# Sheet1.net
KiCad netlist of a schematic drawn in Altium Designer
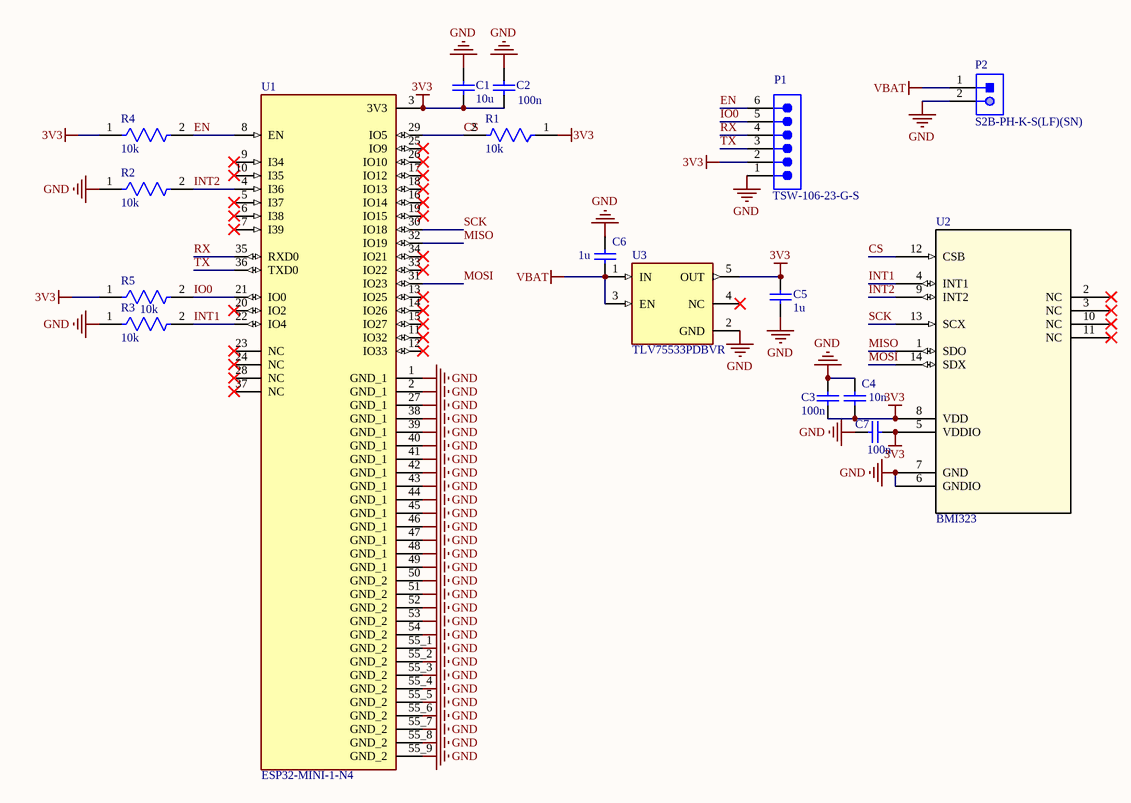
[diagram p0: Sheet1.SchDoc]

(export (version "E")
  (design (tool "Eeschema 10.0.6"))
  (components
    (comp (ref "C1")
      (value "10u")
      (footprint "CAPC2013X145X48NL20T23")
      (fields (field (name "MANUFACTURER") "Vitramon") (field (name "PART NUMBER") "VJ0805Y222JXAAC"))
      (libsource (lib "Altium Content Vault") (part "CAP"))
    )
    (comp (ref "C2")
      (value "100n")
      (footprint "CAPC2013X145X48NL20T23")
      (fields (field (name "MANUFACTURER") "Vitramon") (field (name "PART NUMBER") "VJ0805Y222JXAAC"))
      (libsource (lib "Altium Content Vault") (part "CAP"))
    )
    (comp (ref "C3")
      (value "100n")
      (footprint "CAPC2013X145X48NL20T23")
      (fields (field (name "MANUFACTURER") "Vitramon") (field (name "PART NUMBER") "VJ0805Y222JXAAC"))
      (libsource (lib "Altium Content Vault") (part "CAP"))
    )
    (comp (ref "C4")
      (value "10n")
      (footprint "CAPC2013X145X48NL20T23")
      (fields (field (name "MANUFACTURER") "Vitramon") (field (name "PART NUMBER") "VJ0805Y222JXAAC"))
      (libsource (lib "Altium Content Vault") (part "CAP"))
    )
    (comp (ref "C5")
      (value "1u")
      (footprint "CAPC2013X145X48NL20T23")
      (fields (field (name "MANUFACTURER") "Vitramon") (field (name "PART NUMBER") "VJ0805Y222JXAAC"))
      (libsource (lib "Altium Content Vault") (part "CAP"))
    )
    (comp (ref "C6")
      (value "1u")
      (footprint "CAPC2013X145X48NL20T23")
      (fields (field (name "MANUFACTURER") "Vitramon") (field (name "PART NUMBER") "VJ0805Y222JXAAC"))
      (libsource (lib "Altium Content Vault") (part "CAP"))
    )
    (comp (ref "C7")
      (value "100n")
      (footprint "CAPC2013X145X48NL20T23")
      (fields (field (name "MANUFACTURER") "Vitramon") (field (name "PART NUMBER") "VJ0805Y222JXAAC"))
      (libsource (lib "Altium Content Vault") (part "CAP"))
    )
    (comp (ref "P1")
      (value "TSW-106-23-G-S")
      (footprint "SMTC-TSW-106-23-X-S")
      (description "0.025\" SQ Post Header, Through-hole, Vertical, -55 to 125 degC, 2.54 mm Pitch, 6-Pin, Male, RoHS")
      (fields (field (name "MANUFACTURER") "Samtec"))
      (libsource (lib "Altium Content Vault") (part "SMTC-TSW-106-X-X-S-X"))
    )
    (comp (ref "P2")
      (value "S2B-PH-K-S(LF)(SN)")
      (footprint "JST-S2B-PH-K-S_V")
      (fields (field (name "TOLERANCE") "20%"))
      (libsource (lib "Altium Content Vault") (part "CN-1P-M-R2"))
    )
    (comp (ref "R1")
      (value "10k")
      (footprint "FP-MCU0805-IPC_B")
      (fields (field (name "TOLERANCE") "0.1%"))
      (libsource (lib "Altium Content Vault") (part "1029c3af85768c4190bb7ad29bc67b5"))
    )
    (comp (ref "R2")
      (value "10k")
      (footprint "FP-MCU0805-IPC_B")
      (description "RES 1.05K OHM 0.5% 1/5W 0805")
      (fields (field (name "TOLERANCE") "0.1%"))
      (libsource (lib "Altium Content Vault") (part "1029c3af85768c4190bb7ad29bc67b5"))
    )
    (comp (ref "R3")
      (value "10k")
      (footprint "FP-MCU0805-IPC_B")
      (description "RES 1.05K OHM 0.5% 1/5W 0805")
      (fields (field (name "TOLERANCE") "0.1%"))
      (libsource (lib "Altium Content Vault") (part "1029c3af85768c4190bb7ad29bc67b5"))
    )
    (comp (ref "R4")
      (value "10k")
      (footprint "FP-MCU0805-IPC_B")
      (description "RES 1.05K OHM 0.5% 1/5W 0805")
      (fields (field (name "TOLERANCE") "0.1%"))
      (libsource (lib "Altium Content Vault") (part "1029c3af85768c4190bb7ad29bc67b5"))
    )
    (comp (ref "R5")
      (value "10k")
      (footprint "FP-MCU0805-IPC_B")
      (description "RES 1.05K OHM 0.5% 1/5W 0805")
      (fields (field (name "TOLERANCE") "0.1%"))
      (libsource (lib "Altium Content Vault") (part "1029c3af85768c4190bb7ad29bc67b5"))
    )
    (comp (ref "U1")
      (value "ESP32-MINI-1-N4")
      (footprint "XCVR_ESP32-MINI-1-N4")
      (fields (field (name "MF") "Espressif Systems"))
      (libsource (lib "ESP32-MINI-1-N4") (part "ESP32-MINI-1-N4"))
    )
    (comp (ref "U2")
      (value "BMI323")
      (footprint "BMI323_BOS")
      (description "Description")
      (fields (field (name "COPYRIGHT") "Copyright (C) 2026 Ultra Librarian. All rights reserved."))
      (libsource (lib "BMI323") (part "BMI323"))
    )
    (comp (ref "U3")
      (value "TLV75533PDBVR")
      (footprint "FP-DBV0005A-MFG")
      (description "IC REG LINEAR 3.3V 500MA SOT23-5")
      (fields
        (field (name "MANUFACTURER") "Texas Instruments")
        (field (name "OCTOPART") "https://octopart.com/tlv75533pdbvr-texas+instruments-91272349")
      )
      (libsource (lib "Altium Content Vault") (part "bc27d4aa6bca38f00d7b0ca125c90e0"))
    )
  )
  (nets
    (net (code "1") (name "/CS") (class "Default")
      (node (ref "R1") (pin "2") (pinfunction "2_2") (pintype "passive"))
      (node (ref "U1") (pin "29") (pinfunction "IO5_29") (pintype "bidirectional"))
      (node (ref "U2") (pin "12") (pinfunction "CSB_12") (pintype "input"))
    )
    (net (code "2") (name "/EN") (class "Default")
      (node (ref "P1") (pin "6") (pinfunction "6_6") (pintype "passive"))
      (node (ref "R4") (pin "2") (pinfunction "2_2") (pintype "passive"))
      (node (ref "U1") (pin "8") (pinfunction "EN_8") (pintype "input"))
    )
    (net (code "3") (name "/INT1") (class "Default")
      (node (ref "R3") (pin "2") (pinfunction "2_2") (pintype "passive"))
      (node (ref "U1") (pin "22") (pinfunction "IO4_22") (pintype "bidirectional"))
      (node (ref "U2") (pin "4") (pinfunction "INT1_4") (pintype "bidirectional"))
    )
    (net (code "4") (name "/INT2") (class "Default")
      (node (ref "R2") (pin "2") (pinfunction "2_2") (pintype "passive"))
      (node (ref "U1") (pin "4") (pinfunction "I36_4") (pintype "input"))
      (node (ref "U2") (pin "9") (pinfunction "INT2_9") (pintype "bidirectional"))
    )
    (net (code "5") (name "/IO0") (class "Default")
      (node (ref "P1") (pin "5") (pinfunction "5_5") (pintype "passive"))
      (node (ref "R5") (pin "2") (pinfunction "2_2") (pintype "passive"))
      (node (ref "U1") (pin "21") (pinfunction "IO0_21") (pintype "bidirectional"))
    )
    (net (code "6") (name "/MISO") (class "Default")
      (node (ref "U1") (pin "32") (pinfunction "IO19_32") (pintype "bidirectional"))
      (node (ref "U2") (pin "1") (pinfunction "SDO_1") (pintype "bidirectional"))
    )
    (net (code "7") (name "/MOSI") (class "Default")
      (node (ref "U1") (pin "31") (pinfunction "IO23_31") (pintype "bidirectional"))
      (node (ref "U2") (pin "14") (pinfunction "SDX_14") (pintype "bidirectional"))
    )
    (net (code "8") (name "/RX") (class "Default")
      (node (ref "P1") (pin "4") (pinfunction "4_4") (pintype "passive"))
      (node (ref "U1") (pin "35") (pinfunction "RXD0_35") (pintype "bidirectional"))
    )
    (net (code "9") (name "/SCK") (class "Default")
      (node (ref "U1") (pin "30") (pinfunction "IO18_30") (pintype "bidirectional"))
      (node (ref "U2") (pin "13") (pinfunction "SCX_13") (pintype "input"))
    )
    (net (code "10") (name "/TX") (class "Default")
      (node (ref "P1") (pin "3") (pinfunction "3_3") (pintype "passive"))
      (node (ref "U1") (pin "36") (pinfunction "TXD0_36") (pintype "bidirectional"))
    )
    (net (code "11") (name "3V3") (class "Default")
      (node (ref "C1") (pin "1") (pinfunction "1_1") (pintype "passive"))
      (node (ref "C2") (pin "1") (pinfunction "1_1") (pintype "passive"))
      (node (ref "C3") (pin "1") (pinfunction "1_1") (pintype "passive"))
      (node (ref "C4") (pin "1") (pinfunction "1_1") (pintype "passive"))
      (node (ref "C5") (pin "1") (pinfunction "1_1") (pintype "passive"))
      (node (ref "C7") (pin "1") (pinfunction "1_1") (pintype "passive"))
      (node (ref "P1") (pin "2") (pinfunction "2_2") (pintype "passive"))
      (node (ref "R1") (pin "1") (pinfunction "1_1") (pintype "passive"))
      (node (ref "R4") (pin "1") (pinfunction "1_1") (pintype "passive"))
      (node (ref "R5") (pin "1") (pinfunction "1_1") (pintype "passive"))
      (node (ref "U1") (pin "3") (pinfunction "3V3_3") (pintype "power_in"))
      (node (ref "U2") (pin "5") (pinfunction "VDDIO_5") (pintype "power_in"))
      (node (ref "U2") (pin "8") (pinfunction "VDD_8") (pintype "power_in"))
      (node (ref "U3") (pin "5") (pinfunction "OUT_5") (pintype "output"))
    )
    (net (code "12") (name "GND") (class "Default")
      (node (ref "C1") (pin "2") (pinfunction "2_2") (pintype "passive"))
      (node (ref "C2") (pin "2") (pinfunction "2_2") (pintype "passive"))
      (node (ref "C3") (pin "2") (pinfunction "2_2") (pintype "passive"))
      (node (ref "C4") (pin "2") (pinfunction "2_2") (pintype "passive"))
      (node (ref "C5") (pin "2") (pinfunction "2_2") (pintype "passive"))
      (node (ref "C6") (pin "2") (pinfunction "2_2") (pintype "passive"))
      (node (ref "C7") (pin "2") (pinfunction "2_2") (pintype "passive"))
      (node (ref "P1") (pin "1") (pinfunction "1_1") (pintype "passive"))
      (node (ref "P2") (pin "2") (pinfunction "2_2") (pintype "passive"))
      (node (ref "R2") (pin "1") (pinfunction "1_1") (pintype "passive"))
      (node (ref "R3") (pin "1") (pinfunction "1_1") (pintype "passive"))
      (node (ref "U1") (pin "1") (pinfunction "GND_1_1") (pintype "power_in"))
      (node (ref "U1") (pin "2") (pinfunction "GND_1_2") (pintype "power_in"))
      (node (ref "U1") (pin "27") (pinfunction "GND_1_27") (pintype "power_in"))
      (node (ref "U1") (pin "38") (pinfunction "GND_1_38") (pintype "power_in"))
      (node (ref "U1") (pin "39") (pinfunction "GND_1_39") (pintype "power_in"))
      (node (ref "U1") (pin "40") (pinfunction "GND_1_40") (pintype "power_in"))
      (node (ref "U1") (pin "41") (pinfunction "GND_1_41") (pintype "power_in"))
      (node (ref "U1") (pin "42") (pinfunction "GND_1_42") (pintype "power_in"))
      (node (ref "U1") (pin "43") (pinfunction "GND_1_43") (pintype "power_in"))
      (node (ref "U1") (pin "44") (pinfunction "GND_1_44") (pintype "power_in"))
      (node (ref "U1") (pin "45") (pinfunction "GND_1_45") (pintype "power_in"))
      (node (ref "U1") (pin "46") (pinfunction "GND_1_46") (pintype "power_in"))
      (node (ref "U1") (pin "47") (pinfunction "GND_1_47") (pintype "power_in"))
      (node (ref "U1") (pin "48") (pinfunction "GND_1_48") (pintype "power_in"))
      (node (ref "U1") (pin "49") (pinfunction "GND_1_49") (pintype "power_in"))
      (node (ref "U1") (pin "50") (pinfunction "GND_2_50") (pintype "power_in"))
      (node (ref "U1") (pin "51") (pinfunction "GND_2_51") (pintype "power_in"))
      (node (ref "U1") (pin "52") (pinfunction "GND_2_52") (pintype "power_in"))
      (node (ref "U1") (pin "53") (pinfunction "GND_2_53") (pintype "power_in"))
      (node (ref "U1") (pin "54") (pinfunction "GND_2_54") (pintype "power_in"))
      (node (ref "U1") (pin "55_1") (pinfunction "GND_2_55_1") (pintype "power_in"))
      (node (ref "U1") (pin "55_2") (pinfunction "GND_2_55_2") (pintype "power_in"))
      (node (ref "U1") (pin "55_3") (pinfunction "GND_2_55_3") (pintype "power_in"))
      (node (ref "U1") (pin "55_4") (pinfunction "GND_2_55_4") (pintype "power_in"))
      (node (ref "U1") (pin "55_5") (pinfunction "GND_2_55_5") (pintype "power_in"))
      (node (ref "U1") (pin "55_6") (pinfunction "GND_2_55_6") (pintype "power_in"))
      (node (ref "U1") (pin "55_7") (pinfunction "GND_2_55_7") (pintype "power_in"))
      (node (ref "U1") (pin "55_8") (pinfunction "GND_2_55_8") (pintype "power_in"))
      (node (ref "U1") (pin "55_9") (pinfunction "GND_2_55_9") (pintype "power_in"))
      (node (ref "U2") (pin "6") (pinfunction "GNDIO_6") (pintype "power_in"))
      (node (ref "U2") (pin "7") (pinfunction "GND_7") (pintype "power_in"))
      (node (ref "U3") (pin "2") (pinfunction "GND_2") (pintype "power_in"))
    )
    (net (code "13") (name "VBAT") (class "Default")
      (node (ref "C6") (pin "1") (pinfunction "1_1") (pintype "passive"))
      (node (ref "P2") (pin "1") (pinfunction "1_1") (pintype "passive"))
      (node (ref "U3") (pin "1") (pinfunction "IN_1") (pintype "input"))
      (node (ref "U3") (pin "3") (pinfunction "EN_3") (pintype "input"))
    )
    (net (code "14") (name "unconnected-(U1-I34-Pad9)") (class "Default")
      (node (ref "U1") (pin "9") (pinfunction "I34_9") (pintype "input+no_connect"))
    )
    (net (code "15") (name "unconnected-(U1-I35-Pad10)") (class "Default")
      (node (ref "U1") (pin "10") (pinfunction "I35_10") (pintype "input+no_connect"))
    )
    (net (code "16") (name "unconnected-(U1-I37-Pad5)") (class "Default")
      (node (ref "U1") (pin "5") (pinfunction "I37_5") (pintype "input+no_connect"))
    )
    (net (code "17") (name "unconnected-(U1-I38-Pad6)") (class "Default")
      (node (ref "U1") (pin "6") (pinfunction "I38_6") (pintype "input+no_connect"))
    )
    (net (code "18") (name "unconnected-(U1-I39-Pad7)") (class "Default")
      (node (ref "U1") (pin "7") (pinfunction "I39_7") (pintype "input+no_connect"))
    )
    (net (code "19") (name "unconnected-(U1-IO2-Pad20)") (class "Default")
      (node (ref "U1") (pin "20") (pinfunction "IO2_20") (pintype "bidirectional+no_connect"))
    )
    (net (code "20") (name "unconnected-(U1-IO9-Pad25)") (class "Default")
      (node (ref "U1") (pin "25") (pinfunction "IO9_25") (pintype "bidirectional+no_connect"))
    )
    (net (code "21") (name "unconnected-(U1-IO10-Pad26)") (class "Default")
      (node (ref "U1") (pin "26") (pinfunction "IO10_26") (pintype "bidirectional+no_connect"))
    )
    (net (code "22") (name "unconnected-(U1-IO12-Pad17)") (class "Default")
      (node (ref "U1") (pin "17") (pinfunction "IO12_17") (pintype "bidirectional+no_connect"))
    )
    (net (code "23") (name "unconnected-(U1-IO13-Pad18)") (class "Default")
      (node (ref "U1") (pin "18") (pinfunction "IO13_18") (pintype "bidirectional+no_connect"))
    )
    (net (code "24") (name "unconnected-(U1-IO14-Pad16)") (class "Default")
      (node (ref "U1") (pin "16") (pinfunction "IO14_16") (pintype "bidirectional+no_connect"))
    )
    (net (code "25") (name "unconnected-(U1-IO15-Pad19)") (class "Default")
      (node (ref "U1") (pin "19") (pinfunction "IO15_19") (pintype "bidirectional+no_connect"))
    )
    (net (code "26") (name "unconnected-(U1-IO21-Pad34)") (class "Default")
      (node (ref "U1") (pin "34") (pinfunction "IO21_34") (pintype "bidirectional+no_connect"))
    )
    (net (code "27") (name "unconnected-(U1-IO22-Pad33)") (class "Default")
      (node (ref "U1") (pin "33") (pinfunction "IO22_33") (pintype "bidirectional+no_connect"))
    )
    (net (code "28") (name "unconnected-(U1-IO25-Pad13)") (class "Default")
      (node (ref "U1") (pin "13") (pinfunction "IO25_13") (pintype "bidirectional+no_connect"))
    )
    (net (code "29") (name "unconnected-(U1-IO26-Pad14)") (class "Default")
      (node (ref "U1") (pin "14") (pinfunction "IO26_14") (pintype "bidirectional+no_connect"))
    )
    (net (code "30") (name "unconnected-(U1-IO27-Pad15)") (class "Default")
      (node (ref "U1") (pin "15") (pinfunction "IO27_15") (pintype "bidirectional+no_connect"))
    )
    (net (code "31") (name "unconnected-(U1-IO32-Pad11)") (class "Default")
      (node (ref "U1") (pin "11") (pinfunction "IO32_11") (pintype "bidirectional+no_connect"))
    )
    (net (code "32") (name "unconnected-(U1-IO33-Pad12)") (class "Default")
      (node (ref "U1") (pin "12") (pinfunction "IO33_12") (pintype "bidirectional+no_connect"))
    )
    (net (code "33") (name "unconnected-(U1-NC-Pad23)") (class "Default")
      (node (ref "U1") (pin "23") (pinfunction "NC_23") (pintype "passive+no_connect"))
    )
    (net (code "34") (name "unconnected-(U1-NC-Pad24)") (class "Default")
      (node (ref "U1") (pin "24") (pinfunction "NC_24") (pintype "passive+no_connect"))
    )
    (net (code "35") (name "unconnected-(U1-NC-Pad28)") (class "Default")
      (node (ref "U1") (pin "28") (pinfunction "NC_28") (pintype "passive+no_connect"))
    )
    (net (code "36") (name "unconnected-(U1-NC-Pad37)") (class "Default")
      (node (ref "U1") (pin "37") (pinfunction "NC_37") (pintype "passive+no_connect"))
    )
    (net (code "37") (name "unconnected-(U2-NC-Pad2)") (class "Default")
      (node (ref "U2") (pin "2") (pinfunction "NC_2") (pintype "passive+no_connect"))
    )
    (net (code "38") (name "unconnected-(U2-NC-Pad3)") (class "Default")
      (node (ref "U2") (pin "3") (pinfunction "NC_3") (pintype "passive+no_connect"))
    )
    (net (code "39") (name "unconnected-(U2-NC-Pad10)") (class "Default")
      (node (ref "U2") (pin "10") (pinfunction "NC_10") (pintype "passive+no_connect"))
    )
    (net (code "40") (name "unconnected-(U2-NC-Pad11)") (class "Default")
      (node (ref "U2") (pin "11") (pinfunction "NC_11") (pintype "passive+no_connect"))
    )
    (net (code "41") (name "unconnected-(U3-NC-Pad4)") (class "Default")
      (node (ref "U3") (pin "4") (pinfunction "NC_4") (pintype "passive+no_connect"))
    )
  )
)
